# Power.net
KiCad netlist of a schematic drawn in Altium Designer
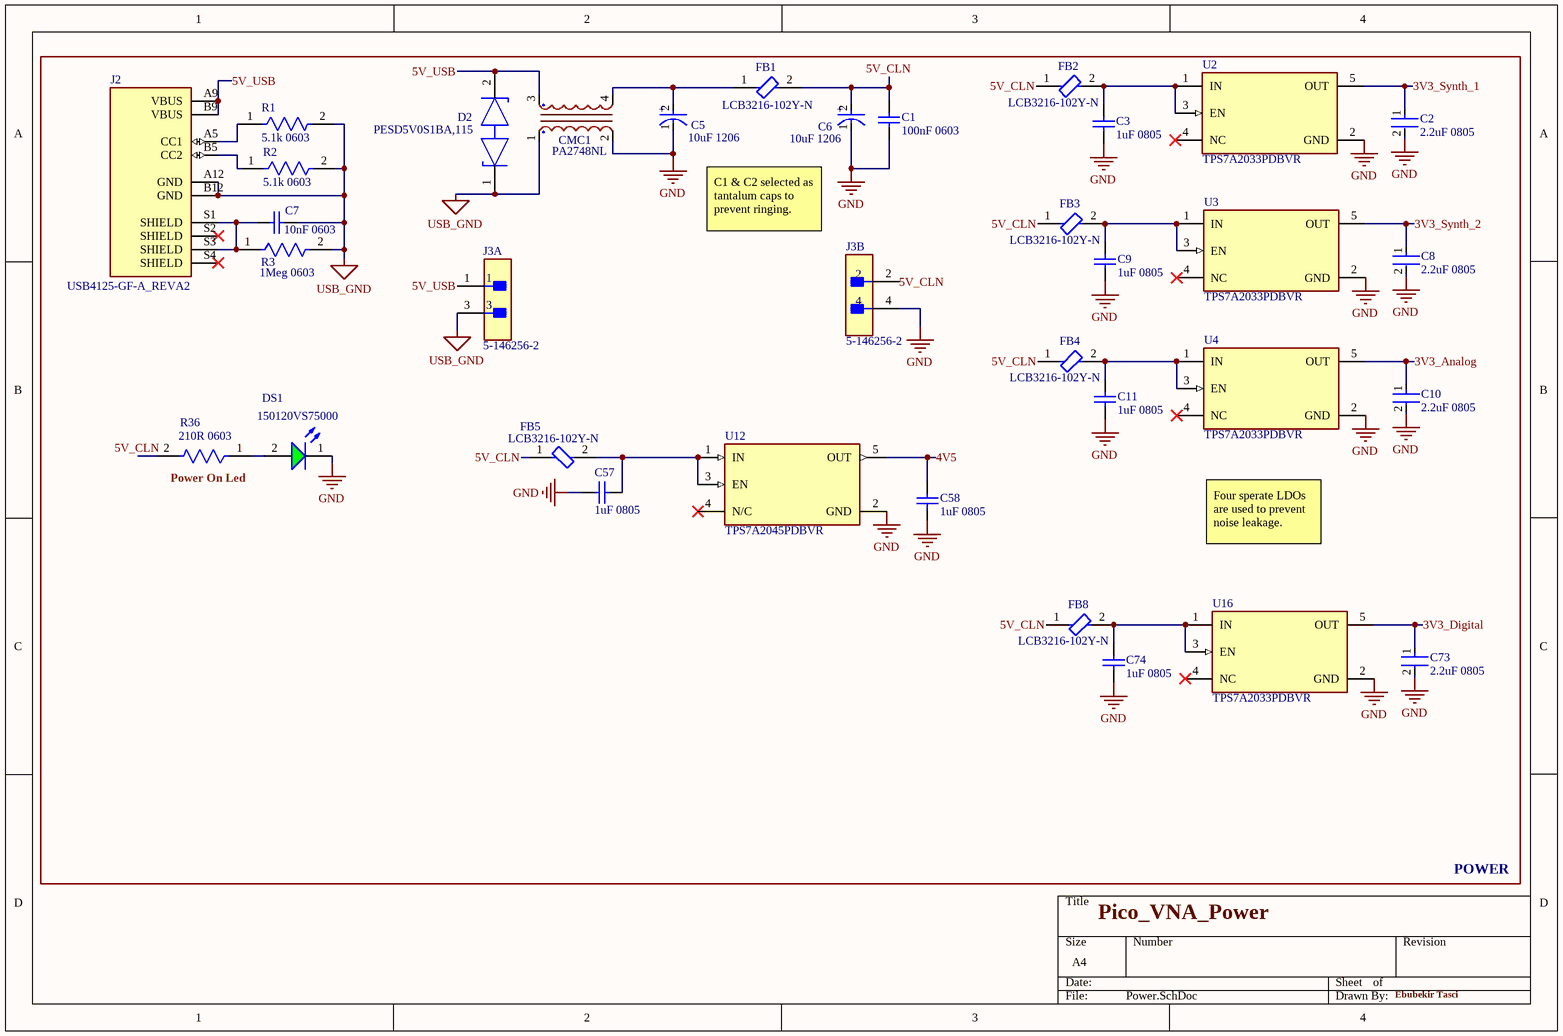
[diagram p0: Power.SchDoc]

(export (version "E")
  (design (tool "Eeschema 10.0.6"))
  (components
    (comp (ref "C1")
      (value "100nF 0603")
      (footprint "CAPC0603(1608)100_N")
      (description "CAP 100nF 25V ±20% 0603 (1608 Metric) Thickness 1mm SMD")
      (fields (field (name "TOLERANCE") "Â±20%"))
      (libsource (lib "Altium Content Vault") (part "CAP"))
    )
    (comp (ref "C2")
      (value "2.2uF 0805")
      (footprint "FP-C0805C225K4RACAUTO-MFG")
      (description "CAP CER 2.2UF 16V X7R 0805")
      (fields (field (name "TOLERANCE") "10%"))
      (libsource (lib "Altium Content Vault") (part "b4654b650e69147ec39a6b967a45e02"))
    )
    (comp (ref "C3")
      (value "1uF 0805")
      (footprint "CAPC2013X145X50NL20T25")
      (fields (field (name "PART NUMBER") "C0805C105J3RACTU") (field (name "MANUFACTURER") "Kemet"))
      (libsource (lib "Altium Content Vault") (part "CAP"))
    )
    (comp (ref "C5")
      (value "10uF 1206")
      (footprint "FP-TAJA-MFG")
      (description "10uF 16V  ±10% 3Ω 1206  SMD Tantalum Capacitor\r\nTAJA106K016RNJ")
      (fields (field (name "VOLTAGE") "16V") (field (name "TOLERANCE") "10%"))
      (libsource (lib "Altium Content Vault") (part "203bc49f2ac43e59fd269a8c329ed05"))
    )
    (comp (ref "C6")
      (value "10uF 1206")
      (footprint "FP-TAJA-MFG")
      (description "10uF 16V  ±10% 3Ω 1206  SMD Tantalum Capacitor\r\nTAJA106K016RNJ")
      (fields (field (name "VOLTAGE") "16V") (field (name "TOLERANCE") "10%"))
      (libsource (lib "Altium Content Vault") (part "203bc49f2ac43e59fd269a8c329ed05"))
    )
    (comp (ref "C7")
      (value "10nF 0603")
      (footprint "CAPC0603(1608)100_N")
      (description "CAP 10nF 25V ±20% 0603 (1608 Metric) Thickness 1mm SMD")
      (fields (field (name "TOLERANCE") "Â±20%"))
      (libsource (lib "Altium Content Vault") (part "CAP"))
    )
    (comp (ref "C8")
      (value "2.2uF 0805")
      (footprint "FP-C0805C225K4RACAUTO-MFG")
      (description "CAP CER 2.2UF 16V X7R 0805")
      (fields (field (name "TOLERANCE") "10%"))
      (libsource (lib "Altium Content Vault") (part "b4654b650e69147ec39a6b967a45e02"))
    )
    (comp (ref "C9")
      (value "1uF 0805")
      (footprint "CAPC2013X145X50NL20T25")
      (fields (field (name "PART NUMBER") "C0805C105J3RACTU") (field (name "MANUFACTURER") "Kemet"))
      (libsource (lib "Altium Content Vault") (part "CAP"))
    )
    (comp (ref "C10")
      (value "2.2uF 0805")
      (footprint "FP-C0805C225K4RACAUTO-MFG")
      (description "CAP CER 2.2UF 16V X7R 0805")
      (fields (field (name "TOLERANCE") "10%"))
      (libsource (lib "Altium Content Vault") (part "b4654b650e69147ec39a6b967a45e02"))
    )
    (comp (ref "C11")
      (value "1uF 0805")
      (footprint "CAPC2013X145X50NL20T25")
      (fields (field (name "PART NUMBER") "C0805C105J3RACTU") (field (name "MANUFACTURER") "Kemet"))
      (libsource (lib "Altium Content Vault") (part "CAP"))
    )
    (comp (ref "C57")
      (value "1uF 0805")
      (footprint "CAPC2013X145X50NL20T25")
      (fields (field (name "PART NUMBER") "C0805C105J3RACTU") (field (name "MANUFACTURER") "Kemet"))
      (libsource (lib "Altium Content Vault") (part "CAP"))
    )
    (comp (ref "C58")
      (value "1uF 0805")
      (footprint "CAPC2013X145X50NL20T25")
      (fields (field (name "PART NUMBER") "C0805C105J3RACTU") (field (name "MANUFACTURER") "Kemet"))
      (libsource (lib "Altium Content Vault") (part "CAP"))
    )
    (comp (ref "C73")
      (value "2.2uF 0805")
      (footprint "FP-C0805C225K4RACAUTO-MFG")
      (description "CAP CER 2.2UF 16V X7R 0805")
      (fields (field (name "TOLERANCE") "10%"))
      (libsource (lib "Altium Content Vault") (part "b4654b650e69147ec39a6b967a45e02"))
    )
    (comp (ref "C74")
      (value "1uF 0805")
      (footprint "CAPC2013X145X50NL20T25")
      (fields (field (name "PART NUMBER") "C0805C105J3RACTU") (field (name "MANUFACTURER") "Kemet"))
      (libsource (lib "Altium Content Vault") (part "CAP"))
    )
    (comp (ref "CMC1")
      (value "PA2748NL")
      (footprint "DFN838P1270X560-4N")
      (description "CHOKE COMMON MODE 1125UH 1.8A SMD")
      (libsource (lib "PA2748NL") (part "PA2748NL"))
    )
    (comp (ref "D2")
      (value "PESD5V0S1BA,115")
      (footprint "FP-SOD323-CA-MFG")
      (description "TVS DIODE 5V 14V SOD323")
      (libsource (lib "Altium Content Vault") (part "f6dbb2535d6b2d347ec798cb4d032a4"))
    )
    (comp (ref "DS1")
      (value "150120VS75000")
      (footprint "WL-SMCW_1206_150120xx75000")
      (description "Led, Green, 570 Nm, 2 V, 30 Ma, 40 Mcd Rohs Compliant: Yes")
      (libsource (lib "Altium Content Vault") (part "LED_Green_2A-1K"))
    )
    (comp (ref "FB1")
      (value "LCB3216-102Y-N")
      (footprint "FP-BLM31-0_2-t1_6-IPC_C")
      (description "Chip Ferrite Bead, 1206, 1kΩ @ 100MHz, max. 0.200Ω, 25%, 2A")
      (libsource (lib "Altium Content Vault") (part "5f30dd21d616792df468990f7003faa"))
    )
    (comp (ref "FB2")
      (value "LCB3216-102Y-N")
      (footprint "FP-BLM31-0_2-t1_6-IPC_C")
      (description "Chip Ferrite Bead, 1206, 1kΩ @ 100MHz, max. 0.200Ω, 25%, 2A")
      (libsource (lib "Altium Content Vault") (part "5f30dd21d616792df468990f7003faa"))
    )
    (comp (ref "FB3")
      (value "LCB3216-102Y-N")
      (footprint "FP-BLM31-0_2-t1_6-IPC_C")
      (description "Chip Ferrite Bead, 1206, 1kΩ @ 100MHz, max. 0.200Ω, 25%, 2A")
      (libsource (lib "Altium Content Vault") (part "5f30dd21d616792df468990f7003faa"))
    )
    (comp (ref "FB4")
      (value "LCB3216-102Y-N")
      (footprint "FP-BLM31-0_2-t1_6-IPC_C")
      (description "Chip Ferrite Bead, 1206, 1kΩ @ 100MHz, max. 0.200Ω, 25%, 2A")
      (libsource (lib "Altium Content Vault") (part "5f30dd21d616792df468990f7003faa"))
    )
    (comp (ref "FB5")
      (value "LCB3216-102Y-N")
      (footprint "FP-BLM31-0_2-t1_6-IPC_C")
      (description "Chip Ferrite Bead, 1206, 1kΩ @ 100MHz, max. 0.200Ω, 25%, 2A")
      (libsource (lib "Altium Content Vault") (part "5f30dd21d616792df468990f7003faa"))
    )
    (comp (ref "FB8")
      (value "LCB3216-102Y-N")
      (footprint "FP-BLM31-0_2-t1_6-IPC_C")
      (description "Chip Ferrite Bead, 1206, 1kΩ @ 100MHz, max. 0.200Ω, 25%, 2A")
      (libsource (lib "Altium Content Vault") (part "5f30dd21d616792df468990f7003faa"))
    )
    (comp (ref "J2")
      (value "USB4125-GF-A_REVA2")
      (footprint "GCT_USB4125-GF-A_REVA2")
      (libsource (lib "Ebubekir Taşcı") (part "USB4125-GF-A_REVA2"))
    )
    (comp (ref "J3")
      (value "5-146256-2")
      (footprint "FP-5-146256-2-MFG")
      (description "CONN HEADER VERT 4POS 2.54MM")
      (libsource (lib "") (part "1621473add15499e993d6bbd36d0f06_1"))
    )
    (comp (ref "R1")
      (value "5.1k 0603")
      (footprint "FP-MCT0603-IPC_B")
      (description "RES SMD 100 OHM 1% 1/8W 0603")
      (fields (field (name "TOLERANCE") "0.1%"))
      (libsource (lib "Altium Content Vault") (part "1029c3af85768c4190bb7ad29bc67b5"))
    )
    (comp (ref "R2")
      (value "5.1k 0603")
      (footprint "FP-MCT0603-IPC_B")
      (description "RES SMD 100 OHM 1% 1/8W 0603")
      (fields (field (name "TOLERANCE") "0.1%"))
      (libsource (lib "Altium Content Vault") (part "1029c3af85768c4190bb7ad29bc67b5"))
    )
    (comp (ref "R3")
      (value "1Meg 0603")
      (footprint "FP-MCT0603-IPC_B")
      (description "RES SMD 1 MEGA OHM 1% 1/8W 0603")
      (fields (field (name "TOLERANCE") "0.1%"))
      (libsource (lib "Altium Content Vault") (part "1029c3af85768c4190bb7ad29bc67b5"))
    )
    (comp (ref "R36")
      (value "210R 0603")
      (footprint "FP-AC0603-IPC_B")
      (description "RES 210Ω 1.00% 0.1W 0603")
      (fields (field (name "TOLERANCE") "1%"))
      (libsource (lib "Altium Content Vault") (part "1029c3af85768c4190bb7ad29bc67b5"))
    )
    (comp (ref "U2")
      (value "TPS7A2033PDBVR")
      (footprint "FP-DBV0005A-MFG")
      (description "IC REG LINEAR 3.3V 300MA SOT23-5")
      (libsource (lib "Altium Content Vault") (part "76aa7ad0ceb1012e0d85aeafc53095f"))
    )
    (comp (ref "U3")
      (value "TPS7A2033PDBVR")
      (footprint "FP-DBV0005A-MFG")
      (description "IC REG LINEAR 3.3V 300MA SOT23-5")
      (libsource (lib "Altium Content Vault") (part "76aa7ad0ceb1012e0d85aeafc53095f"))
    )
    (comp (ref "U4")
      (value "TPS7A2033PDBVR")
      (footprint "FP-DBV0005A-MFG")
      (description "IC REG LINEAR 3.3V 300MA SOT23-5")
      (libsource (lib "Altium Content Vault") (part "76aa7ad0ceb1012e0d85aeafc53095f"))
    )
    (comp (ref "U12")
      (value "TPS7A2045PDBVR")
      (footprint "SOT95P280X145-5N")
      (fields (field (name "MF") "{'manufacturer': u'Texas Instruments'}"))
      (libsource (lib "Ebubekir Taşcı") (part "TPS7A2045PDBVR"))
    )
    (comp (ref "U16")
      (value "TPS7A2033PDBVR")
      (footprint "FP-DBV0005A-MFG")
      (description "IC REG LINEAR 3.3V 300MA SOT23-5")
      (libsource (lib "Altium Content Vault") (part "76aa7ad0ceb1012e0d85aeafc53095f"))
    )
  )
  (nets
    (net (code "1") (name "/3V3_Analog") (class "Default")
      (node (ref "C10") (pin "1") (pinfunction "1_1") (pintype "passive"))
      (node (ref "U4") (pin "5") (pinfunction "OUT_5") (pintype "passive"))
    )
    (net (code "2") (name "/3V3_Digital") (class "Default")
      (node (ref "C73") (pin "1") (pinfunction "1_1") (pintype "passive"))
      (node (ref "U16") (pin "5") (pinfunction "OUT_5") (pintype "passive"))
    )
    (net (code "3") (name "/3V3_Synth_1") (class "Default")
      (node (ref "C2") (pin "1") (pinfunction "1_1") (pintype "passive"))
      (node (ref "U2") (pin "5") (pinfunction "OUT_5") (pintype "passive"))
    )
    (net (code "4") (name "/3V3_Synth_2") (class "Default")
      (node (ref "C8") (pin "1") (pinfunction "1_1") (pintype "passive"))
      (node (ref "U3") (pin "5") (pinfunction "OUT_5") (pintype "passive"))
    )
    (net (code "5") (name "/4V5") (class "Default")
      (node (ref "C58") (pin "2") (pinfunction "2_2") (pintype "passive"))
      (node (ref "U12") (pin "5") (pinfunction "OUT_5") (pintype "output"))
    )
    (net (code "6") (name "/5V_CLN") (class "Default")
      (node (ref "C1") (pin "2") (pinfunction "2_2") (pintype "passive"))
      (node (ref "C6") (pin "2") (pinfunction "A_2") (pintype "passive"))
      (node (ref "FB1") (pin "2") (pinfunction "2_2") (pintype "passive"))
      (node (ref "FB2") (pin "1") (pinfunction "1_1") (pintype "passive"))
      (node (ref "FB3") (pin "1") (pinfunction "1_1") (pintype "passive"))
      (node (ref "FB4") (pin "1") (pinfunction "1_1") (pintype "passive"))
      (node (ref "FB5") (pin "1") (pinfunction "1_1") (pintype "passive"))
      (node (ref "FB8") (pin "1") (pinfunction "1_1") (pintype "passive"))
      (node (ref "J3") (pin "2") (pinfunction "2_2") (pintype "passive"))
      (node (ref "R36") (pin "2") (pinfunction "2_2") (pintype "passive"))
    )
    (net (code "7") (name "/5V_USB") (class "Default")
      (node (ref "CMC1") (pin "3") (pinfunction "3_3") (pintype "passive"))
      (node (ref "D2") (pin "2") (pinfunction "K2_2") (pintype "passive"))
      (node (ref "J2") (pin "A9") (pinfunction "VBUS_A9") (pintype "power_in"))
      (node (ref "J2") (pin "B9") (pinfunction "VBUS_B9") (pintype "power_in"))
      (node (ref "J3") (pin "1") (pinfunction "1_1") (pintype "passive"))
    )
    (net (code "8") (name "GND") (class "Default")
      (node (ref "C1") (pin "1") (pinfunction "1_1") (pintype "passive"))
      (node (ref "C10") (pin "2") (pinfunction "2_2") (pintype "passive"))
      (node (ref "C11") (pin "1") (pinfunction "1_1") (pintype "passive"))
      (node (ref "C2") (pin "2") (pinfunction "2_2") (pintype "passive"))
      (node (ref "C3") (pin "1") (pinfunction "1_1") (pintype "passive"))
      (node (ref "C5") (pin "1") (pinfunction "C_1") (pintype "passive"))
      (node (ref "C57") (pin "1") (pinfunction "1_1") (pintype "passive"))
      (node (ref "C58") (pin "1") (pinfunction "1_1") (pintype "passive"))
      (node (ref "C6") (pin "1") (pinfunction "C_1") (pintype "passive"))
      (node (ref "C73") (pin "2") (pinfunction "2_2") (pintype "passive"))
      (node (ref "C74") (pin "1") (pinfunction "1_1") (pintype "passive"))
      (node (ref "C8") (pin "2") (pinfunction "2_2") (pintype "passive"))
      (node (ref "C9") (pin "1") (pinfunction "1_1") (pintype "passive"))
      (node (ref "CMC1") (pin "2") (pinfunction "2_2") (pintype "passive"))
      (node (ref "DS1") (pin "1") (pinfunction "K_1") (pintype "passive"))
      (node (ref "J3") (pin "4") (pinfunction "4_4") (pintype "passive"))
      (node (ref "U12") (pin "2") (pinfunction "GND_2") (pintype "power_in"))
      (node (ref "U16") (pin "2") (pinfunction "GND_2") (pintype "power_in"))
      (node (ref "U2") (pin "2") (pinfunction "GND_2") (pintype "power_in"))
      (node (ref "U3") (pin "2") (pinfunction "GND_2") (pintype "power_in"))
      (node (ref "U4") (pin "2") (pinfunction "GND_2") (pintype "power_in"))
    )
    (net (code "9") (name "Net-(C5-A)") (class "Default")
      (node (ref "C5") (pin "2") (pinfunction "A_2") (pintype "passive"))
      (node (ref "CMC1") (pin "4") (pinfunction "4_4") (pintype "passive"))
      (node (ref "FB1") (pin "1") (pinfunction "1_1") (pintype "passive"))
    )
    (net (code "10") (name "Net-(C7-Pad2)") (class "Default")
      (node (ref "C7") (pin "2") (pinfunction "2_2") (pintype "passive"))
      (node (ref "J2") (pin "S1") (pinfunction "SHIELD_S1") (pintype "passive"))
      (node (ref "J2") (pin "S3") (pinfunction "SHIELD_S3") (pintype "passive"))
      (node (ref "R3") (pin "1") (pinfunction "1_1") (pintype "passive"))
    )
    (net (code "11") (name "Net-(DS1-A)") (class "Default")
      (node (ref "DS1") (pin "2") (pinfunction "A_2") (pintype "passive"))
      (node (ref "R36") (pin "1") (pinfunction "1_1") (pintype "passive"))
    )
    (net (code "12") (name "Net-(J2-CC1)") (class "Default")
      (node (ref "J2") (pin "A5") (pinfunction "CC1_A5") (pintype "bidirectional"))
      (node (ref "R1") (pin "1") (pinfunction "1_1") (pintype "passive"))
    )
    (net (code "13") (name "Net-(J2-CC2)") (class "Default")
      (node (ref "J2") (pin "B5") (pinfunction "CC2_B5") (pintype "bidirectional"))
      (node (ref "R2") (pin "1") (pinfunction "1_1") (pintype "passive"))
    )
    (net (code "14") (name "Net-(U2-EN)") (class "Default")
      (node (ref "C3") (pin "2") (pinfunction "2_2") (pintype "passive"))
      (node (ref "FB2") (pin "2") (pinfunction "2_2") (pintype "passive"))
      (node (ref "U2") (pin "1") (pinfunction "IN_1") (pintype "power_in"))
      (node (ref "U2") (pin "3") (pinfunction "EN_3") (pintype "input"))
    )
    (net (code "15") (name "Net-(U3-EN)") (class "Default")
      (node (ref "C9") (pin "2") (pinfunction "2_2") (pintype "passive"))
      (node (ref "FB3") (pin "2") (pinfunction "2_2") (pintype "passive"))
      (node (ref "U3") (pin "1") (pinfunction "IN_1") (pintype "power_in"))
      (node (ref "U3") (pin "3") (pinfunction "EN_3") (pintype "input"))
    )
    (net (code "16") (name "Net-(U4-EN)") (class "Default")
      (node (ref "C11") (pin "2") (pinfunction "2_2") (pintype "passive"))
      (node (ref "FB4") (pin "2") (pinfunction "2_2") (pintype "passive"))
      (node (ref "U4") (pin "1") (pinfunction "IN_1") (pintype "power_in"))
      (node (ref "U4") (pin "3") (pinfunction "EN_3") (pintype "input"))
    )
    (net (code "17") (name "Net-(U12-EN)") (class "Default")
      (node (ref "C57") (pin "2") (pinfunction "2_2") (pintype "passive"))
      (node (ref "FB5") (pin "2") (pinfunction "2_2") (pintype "passive"))
      (node (ref "U12") (pin "1") (pinfunction "IN_1") (pintype "input"))
      (node (ref "U12") (pin "3") (pinfunction "EN_3") (pintype "input"))
    )
    (net (code "18") (name "Net-(U16-EN)") (class "Default")
      (node (ref "C74") (pin "2") (pinfunction "2_2") (pintype "passive"))
      (node (ref "FB8") (pin "2") (pinfunction "2_2") (pintype "passive"))
      (node (ref "U16") (pin "1") (pinfunction "IN_1") (pintype "power_in"))
      (node (ref "U16") (pin "3") (pinfunction "EN_3") (pintype "input"))
    )
    (net (code "19") (name "USB_GND") (class "Default")
      (node (ref "C7") (pin "1") (pinfunction "1_1") (pintype "passive"))
      (node (ref "CMC1") (pin "1") (pinfunction "1_1") (pintype "passive"))
      (node (ref "D2") (pin "1") (pinfunction "K1_1") (pintype "passive"))
      (node (ref "J2") (pin "A12") (pinfunction "GND_A12") (pintype "power_in"))
      (node (ref "J2") (pin "B12") (pinfunction "GND_B12") (pintype "power_in"))
      (node (ref "J3") (pin "3") (pinfunction "3_3") (pintype "passive"))
      (node (ref "R1") (pin "2") (pinfunction "2_2") (pintype "passive"))
      (node (ref "R2") (pin "2") (pinfunction "2_2") (pintype "passive"))
      (node (ref "R3") (pin "2") (pinfunction "2_2") (pintype "passive"))
    )
    (net (code "20") (name "unconnected-(J2-SHIELD-PadS2)") (class "Default")
      (node (ref "J2") (pin "S2") (pinfunction "SHIELD_S2") (pintype "passive+no_connect"))
    )
    (net (code "21") (name "unconnected-(J2-SHIELD-PadS4)") (class "Default")
      (node (ref "J2") (pin "S4") (pinfunction "SHIELD_S4") (pintype "passive+no_connect"))
    )
    (net (code "22") (name "unconnected-(U2-NC-Pad4)") (class "Default")
      (node (ref "U2") (pin "4") (pinfunction "NC_4") (pintype "passive+no_connect"))
    )
    (net (code "23") (name "unconnected-(U3-NC-Pad4)") (class "Default")
      (node (ref "U3") (pin "4") (pinfunction "NC_4") (pintype "passive+no_connect"))
    )
    (net (code "24") (name "unconnected-(U4-NC-Pad4)") (class "Default")
      (node (ref "U4") (pin "4") (pinfunction "NC_4") (pintype "passive+no_connect"))
    )
    (net (code "25") (name "unconnected-(U12-N{slash}C-Pad4)") (class "Default")
      (node (ref "U12") (pin "4") (pinfunction "N/C_4") (pintype "passive+no_connect"))
    )
    (net (code "26") (name "unconnected-(U16-NC-Pad4)") (class "Default")
      (node (ref "U16") (pin "4") (pinfunction "NC_4") (pintype "passive+no_connect"))
    )
  )
)
